# LedsAndButtons.net
KiCad netlist of a schematic drawn in Altium Designer
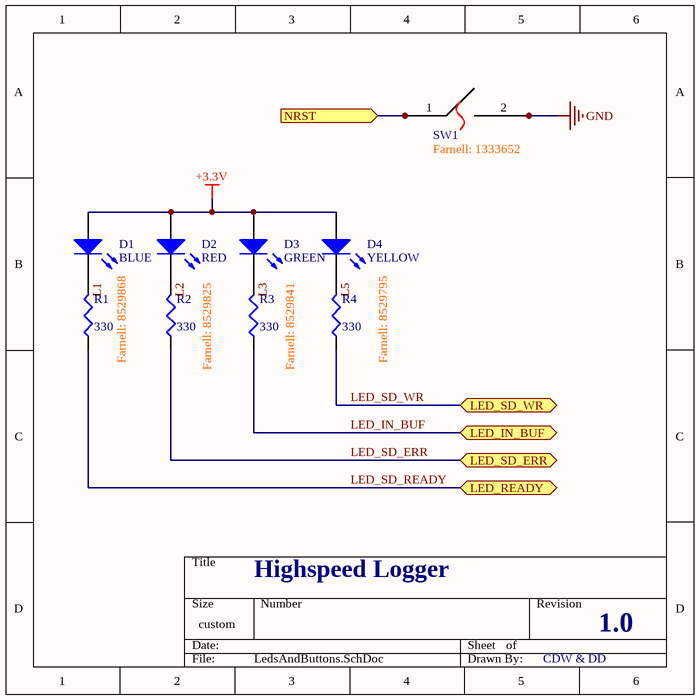
[diagram p0: LedsAndButtons.SchDoc]

(export (version "E")
  (design (tool "Eeschema 10.0.6"))
  (components
    (comp (ref "D1")
      (value "BLUE")
      (footprint "KP-1608SURC_R")
      (description "Typical RED, GREEN, YELLOW, AMBER GaAs LED")
      (fields (field (name "FARNELL") "8529868") (field (name "PUBLISHER") "Altium Limited"))
      (libsource (lib "Miscellaneous Devices") (part "LED2"))
    )
    (comp (ref "D2")
      (value "RED")
      (footprint "KP-1608SURC_B")
      (description "Typical RED, GREEN, YELLOW, AMBER GaAs LED")
      (fields (field (name "FARNELL") "8529825") (field (name "PUBLISHER") "Altium Limited"))
      (libsource (lib "Miscellaneous Devices") (part "LED2"))
    )
    (comp (ref "D3")
      (value "GREEN")
      (footprint "KP-1608SURC_Y")
      (description "Typical RED, GREEN, YELLOW, AMBER GaAs LED")
      (fields (field (name "FARNELL") "8529841") (field (name "PUBLISHER") "Altium Limited"))
      (libsource (lib "Miscellaneous Devices") (part "LED2"))
    )
    (comp (ref "D4")
      (value "YELLOW")
      (footprint "KP-1608SURC_G")
      (description "Typical RED, GREEN, YELLOW, AMBER GaAs LED")
      (fields (field (name "FARNELL") "8529795") (field (name "PUBLISHER") "Altium Limited"))
      (libsource (lib "Miscellaneous Devices") (part "LED2"))
    )
    (comp (ref "R1")
      (value "330")
      (footprint "V0402RES")
      (description "Resistor")
      (fields (field (name "Comment") "Res3") (field (name "PUBLISHER") "Altium Limited"))
      (libsource (lib "Miscellaneous Devices") (part "Res3"))
    )
    (comp (ref "R2")
      (value "330")
      (footprint "V0402RES")
      (description "Resistor")
      (fields (field (name "Comment") "Res3") (field (name "PUBLISHER") "Altium Limited"))
      (libsource (lib "Miscellaneous Devices") (part "Res3"))
    )
    (comp (ref "R3")
      (value "330")
      (footprint "V0402RES")
      (description "Resistor")
      (fields (field (name "Comment") "Res3") (field (name "PUBLISHER") "Altium Limited"))
      (libsource (lib "Miscellaneous Devices") (part "Res3"))
    )
    (comp (ref "R4")
      (value "330")
      (footprint "V0402RES")
      (description "Resistor")
      (fields (field (name "Comment") "Res3") (field (name "PUBLISHER") "Altium Limited"))
      (libsource (lib "Miscellaneous Devices") (part "Res3"))
    )
    (comp (ref "SW1")
      (value "Tactile OMRON B3U-1000P")
      (footprint "TACTILE-B3U-1000P")
      (fields (field (name "FARNELL") "1333652"))
      (libsource (lib "MiscComponents") (part "Tactile OMRON B3U-1000P"))
    )
  )
  (nets
    (net (code "1") (name "+3.3V") (class "Default")
      (node (ref "D1") (pin "1") (pinfunction "A_1") (pintype "passive"))
      (node (ref "D2") (pin "1") (pinfunction "A_1") (pintype "passive"))
      (node (ref "D3") (pin "1") (pinfunction "A_1") (pintype "passive"))
      (node (ref "D4") (pin "1") (pinfunction "A_1") (pintype "passive"))
    )
    (net (code "2") (name "/L1") (class "Default")
      (node (ref "D1") (pin "2") (pinfunction "K_2") (pintype "passive"))
      (node (ref "R1") (pin "2") (pinfunction "2_2") (pintype "passive"))
    )
    (net (code "3") (name "/L2") (class "Default")
      (node (ref "D2") (pin "2") (pinfunction "K_2") (pintype "passive"))
      (node (ref "R2") (pin "2") (pinfunction "2_2") (pintype "passive"))
    )
    (net (code "4") (name "/L3") (class "Default")
      (node (ref "D3") (pin "2") (pinfunction "K_2") (pintype "passive"))
      (node (ref "R3") (pin "2") (pinfunction "2_2") (pintype "passive"))
    )
    (net (code "5") (name "/L5") (class "Default")
      (node (ref "D4") (pin "2") (pinfunction "K_2") (pintype "passive"))
      (node (ref "R4") (pin "2") (pinfunction "2_2") (pintype "passive"))
    )
    (net (code "6") (name "/LED_IN_BUF") (class "Default")
      (node (ref "R3") (pin "1") (pinfunction "1_1") (pintype "passive"))
    )
    (net (code "7") (name "/LED_SD_ERR") (class "Default")
      (node (ref "R2") (pin "1") (pinfunction "1_1") (pintype "passive"))
    )
    (net (code "8") (name "/LED_SD_READY") (class "Default")
      (node (ref "R1") (pin "1") (pinfunction "1_1") (pintype "passive"))
    )
    (net (code "9") (name "/LED_SD_WR") (class "Default")
      (node (ref "R4") (pin "1") (pinfunction "1_1") (pintype "passive"))
    )
    (net (code "10") (name "/NRST") (class "Default")
      (node (ref "SW1") (pin "1") (pinfunction "1_1") (pintype "passive"))
    )
    (net (code "11") (name "GND") (class "Default")
      (node (ref "SW1") (pin "2") (pinfunction "2_2") (pintype "passive"))
    )
  )
)
